# Microcontroller.net
KiCad netlist of a schematic drawn in Altium Designer
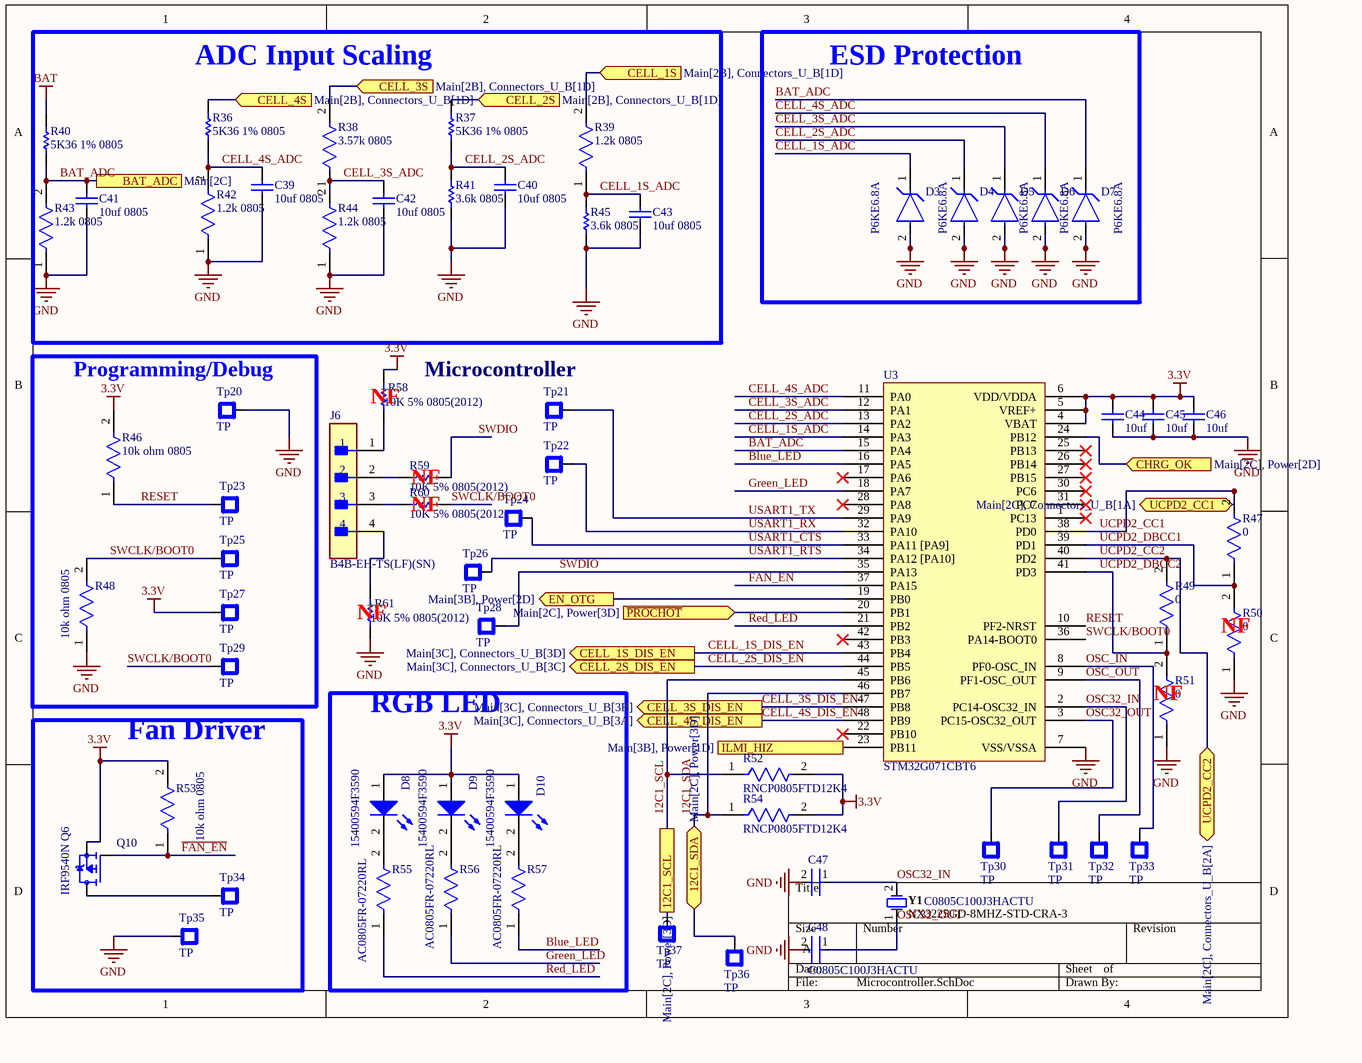
[diagram p0: Microcontroller.SchDoc]

(export (version "E")
  (design (tool "Eeschema 10.0.6"))
  (components
    (comp (ref "C39")
      (value "10uf 0805")
      (footprint "CAPC2013X145X50NL20T20")
      (fields (field (name "PART NUMBER") "VJ0805Y105KXQRW1BC") (field (name "MANUFACTURER") "Vitramon"))
      (libsource (lib "Altium Content Vault") (part "CAP"))
    )
    (comp (ref "C40")
      (value "10uf 0805")
      (footprint "CAPC2013X145X50NL20T20")
      (fields (field (name "PART NUMBER") "VJ0805Y105KXQRW1BC") (field (name "MANUFACTURER") "Vitramon"))
      (libsource (lib "Altium Content Vault") (part "CAP"))
    )
    (comp (ref "C41")
      (value "10uf 0805")
      (footprint "CAPC2013X145X50NL20T20")
      (fields (field (name "PART NUMBER") "VJ0805Y105KXQRW1BC") (field (name "MANUFACTURER") "Vitramon"))
      (libsource (lib "Altium Content Vault") (part "CAP"))
    )
    (comp (ref "C42")
      (value "10uf 0805")
      (footprint "CAPC2013X145X50NL20T20")
      (fields (field (name "PART NUMBER") "VJ0805Y105KXQRW1BC") (field (name "MANUFACTURER") "Vitramon"))
      (libsource (lib "Altium Content Vault") (part "CAP"))
    )
    (comp (ref "C43")
      (value "10uf 0805")
      (footprint "CAPC2013X145X50NL20T20")
      (fields (field (name "PART NUMBER") "VJ0805Y105KXQRW1BC") (field (name "MANUFACTURER") "Vitramon"))
      (libsource (lib "Altium Content Vault") (part "CAP"))
    )
    (comp (ref "C44")
      (value "10uf")
      (footprint "CAPC2013X145X50LL20T25")
      (fields (field (name "MANUFACTURER") "Kemet") (field (name "PART NUMBER") "C0805C106K8RACTU"))
      (libsource (lib "Altium Content Vault") (part "CAP"))
    )
    (comp (ref "C45")
      (value "10uf")
      (footprint "CAPC2013X145X50LL20T25")
      (fields (field (name "MANUFACTURER") "Kemet") (field (name "PART NUMBER") "C0805C106K8RACTU"))
      (libsource (lib "Altium Content Vault") (part "CAP"))
    )
    (comp (ref "C46")
      (value "10uf")
      (footprint "CAPC2013X145X50LL20T25")
      (fields (field (name "MANUFACTURER") "Kemet") (field (name "PART NUMBER") "C0805C106K8RACTU"))
      (libsource (lib "Altium Content Vault") (part "CAP"))
    )
    (comp (ref "C47")
      (value "C0805C100J3HACTU")
      (footprint "FP-C0805C-DN-MFG")
      (description "C0805 10 pF X8R 30ppm/°C 5.00% 25 V")
      (fields (field (name "TOLERANCE") "0.05") (field (name "MANUFACTURER") "KEMET"))
      (libsource (lib "Altium Content Vault") (part "b4654b650e69147ec39a6b967a45e02"))
    )
    (comp (ref "C48")
      (value "C0805C100J3HACTU")
      (footprint "FP-C0805C-DN-MFG")
      (description "C0805 10 pF X8R 30ppm/°C 5.00% 25 V")
      (fields (field (name "TOLERANCE") "0.05") (field (name "MANUFACTURER") "KEMET"))
      (libsource (lib "Altium Content Vault") (part "b4654b650e69147ec39a6b967a45e02"))
    )
    (comp (ref "D3")
      (value "P6KE6.8A")
      (footprint "FP-P6KE-MFG")
      (description "TVS DIODE 5.8V 10.5V DO204AC")
      (fields
        (field (name "MANUFACTURER") "Littelfuse Inc")
        (field (name "OCTOPART") "https://octopart.com/p6ke6.8a-littelfuse-20808")
      )
      (libsource (lib "Altium Content Vault") (part "f813f71cba58e380607f5dd3caf9714"))
    )
    (comp (ref "D4")
      (value "P6KE6.8A")
      (footprint "FP-P6KE-MFG")
      (description "TVS DIODE 5.8V 10.5V DO204AC")
      (fields
        (field (name "MANUFACTURER") "Littelfuse Inc")
        (field (name "OCTOPART") "https://octopart.com/p6ke6.8a-littelfuse-20808")
      )
      (libsource (lib "Altium Content Vault") (part "f813f71cba58e380607f5dd3caf9714"))
    )
    (comp (ref "D5")
      (value "P6KE6.8A")
      (footprint "FP-P6KE-MFG")
      (description "TVS DIODE 5.8V 10.5V DO204AC")
      (fields
        (field (name "MANUFACTURER") "Littelfuse Inc")
        (field (name "OCTOPART") "https://octopart.com/p6ke6.8a-littelfuse-20808")
      )
      (libsource (lib "Altium Content Vault") (part "f813f71cba58e380607f5dd3caf9714"))
    )
    (comp (ref "D6")
      (value "P6KE6.8A")
      (footprint "FP-P6KE-MFG")
      (description "TVS DIODE 5.8V 10.5V DO204AC")
      (fields
        (field (name "MANUFACTURER") "Littelfuse Inc")
        (field (name "OCTOPART") "https://octopart.com/p6ke6.8a-littelfuse-20808")
      )
      (libsource (lib "Altium Content Vault") (part "f813f71cba58e380607f5dd3caf9714"))
    )
    (comp (ref "D7")
      (value "P6KE6.8A")
      (footprint "FP-P6KE-MFG")
      (description "TVS DIODE 5.8V 10.5V DO204AC")
      (fields
        (field (name "MANUFACTURER") "Littelfuse Inc")
        (field (name "OCTOPART") "https://octopart.com/p6ke6.8a-littelfuse-20808")
      )
      (libsource (lib "Altium Content Vault") (part "f813f71cba58e380607f5dd3caf9714"))
    )
    (comp (ref "D8")
      (value "15400594F3590")
      (footprint "WL-TIRC_5mm")
      (description "Led, 5Mm, 940Nm, 30Mw/Sr, Th Rohs Compliant: Yes")
      (libsource (lib "Altium Content Vault") (part "LED_Infrared_1A-2K"))
    )
    (comp (ref "D9")
      (value "15400594F3590")
      (footprint "WL-TIRC_5mm")
      (description "Led, 5Mm, 940Nm, 30Mw/Sr, Th Rohs Compliant: Yes")
      (libsource (lib "Altium Content Vault") (part "LED_Infrared_1A-2K"))
    )
    (comp (ref "D10")
      (value "15400594F3590")
      (footprint "WL-TIRC_5mm")
      (description "Led, 5Mm, 940Nm, 30Mw/Sr, Th Rohs Compliant: Yes")
      (libsource (lib "Altium Content Vault") (part "LED_Infrared_1A-2K"))
    )
    (comp (ref "J6")
      (value "B4B-EH-TS(LF)(SN)")
      (footprint "FP-B4B-EH-TS_LF_SN-MFG")
      (description "CONN HEADER EH TOP 4POS 2.5MM")
      (libsource (lib "Altium Content Vault") (part "299a8cea1bdcbc3624fe62c390fa72c"))
    )
    (comp (ref "Q10")
      (value "IRF9540N Q6")
      (footprint "TO254P1041X444X1930-3")
      (description "P-Channel 100 V 23A (Tc) 3.1W (Ta), 110W (Tc)")
      (fields (field (name "MF") "Infineon Technologies") (field (name "MP") "IRF9540N"))
      (libsource (lib "power_schi") (part "IRF9540N Q6"))
    )
    (comp (ref "R36")
      (value "5K36 1% 0805")
      (footprint "RESC0805(2012)_M")
      (description "5K36 0.125W 1% 0805 (2012 Metric)  SMD")
      (fields (field (name "POWER") "0.125 W") (field (name "TOLERANCE") "1 %"))
      (libsource (lib "Altium Content Vault") (part "RES"))
    )
    (comp (ref "R37")
      (value "5K36 1% 0805")
      (footprint "RESC0805(2012)_M")
      (description "5K36 0.125W 1% 0805 (2012 Metric)  SMD")
      (fields (field (name "POWER") "0.125 W") (field (name "TOLERANCE") "1 %"))
      (libsource (lib "Altium Content Vault") (part "RES"))
    )
    (comp (ref "R38")
      (value "3.57k 0805")
      (footprint "FP-RT0805-MFG")
      (description "RES 357K OHM 1/8W .1% SMD 0805")
      (fields
        (field (name "OCTOPART") "https://octopart.com/rt0805brd07357kl-yageo-1483813")
        (field (name "MANUFACTURER") "Yageo")
      )
      (libsource (lib "Altium Content Vault") (part "1029c3af85768c4190bb7ad29bc67b5"))
    )
    (comp (ref "R39")
      (value "1.2k 0805")
      (footprint "FP-RMCF0805-IPC_A")
      (description "1.2kΩ ±5% 0.125W 0805 Thick Film Chip Resistor AEC-Q200 compliant")
      (fields (field (name "TOLERANCE") "5%"))
      (libsource (lib "Altium Content Vault") (part "1029c3af85768c4190bb7ad29bc67b5"))
    )
    (comp (ref "R40")
      (value "5K36 1% 0805")
      (footprint "RESC0805(2012)_M")
      (description "5K36 0.125W 1% 0805 (2012 Metric)  SMD")
      (fields (field (name "POWER") "0.125 W") (field (name "TOLERANCE") "1 %"))
      (libsource (lib "Altium Content Vault") (part "RES"))
    )
    (comp (ref "R41")
      (value "3.6k 0805")
      (footprint "RESC0805(2012)_L")
      (description "3K6 0.125W 5% 0805 (2012 Metric)  SMD")
      (fields (field (name "TOLERANCE") "5 %") (field (name "POWER") "0.125 W"))
      (libsource (lib "Altium Content Vault") (part "RES"))
    )
    (comp (ref "R42")
      (value "1.2k 0805")
      (footprint "FP-RMCF0805-IPC_A")
      (description "1.2kΩ ±5% 0.125W 0805 Thick Film Chip Resistor AEC-Q200 compliant")
      (fields (field (name "TOLERANCE") "5%"))
      (libsource (lib "Altium Content Vault") (part "1029c3af85768c4190bb7ad29bc67b5"))
    )
    (comp (ref "R43")
      (value "1.2k 0805")
      (footprint "FP-RMCF0805-IPC_A")
      (description "1.2kΩ ±5% 0.125W 0805 Thick Film Chip Resistor AEC-Q200 compliant")
      (fields (field (name "TOLERANCE") "5%"))
      (libsource (lib "Altium Content Vault") (part "1029c3af85768c4190bb7ad29bc67b5"))
    )
    (comp (ref "R44")
      (value "1.2k 0805")
      (footprint "FP-RMCF0805-IPC_A")
      (description "1.2kΩ ±5% 0.125W 0805 Thick Film Chip Resistor AEC-Q200 compliant")
      (fields (field (name "TOLERANCE") "5%"))
      (libsource (lib "Altium Content Vault") (part "1029c3af85768c4190bb7ad29bc67b5"))
    )
    (comp (ref "R45")
      (value "3.6k 0805")
      (footprint "RESC0805(2012)_L")
      (description "3K6 0.125W 5% 0805 (2012 Metric)  SMD")
      (fields (field (name "TOLERANCE") "5 %") (field (name "POWER") "0.125 W"))
      (libsource (lib "Altium Content Vault") (part "RES"))
    )
    (comp (ref "R46")
      (value "10k ohm 0805")
      (footprint "FP-MCU0805-IPC_C")
      (description "RES 1.05K OHM 0.5% 1/5W 0805")
      (fields (field (name "TOLERANCE") "0.1%"))
      (libsource (lib "Altium Content Vault") (part "1029c3af85768c4190bb7ad29bc67b5"))
    )
    (comp (ref "R47")
      (value "0")
      (footprint "FP-HCJ0805-MFG")
      (description "RES 0 OHM JUMPER 1/2W 0805")
      (libsource (lib "Altium Content Vault") (part "1029c3af85768c4190bb7ad29bc67b5"))
    )
    (comp (ref "R48")
      (value "10k ohm 0805")
      (footprint "FP-MCU0805-IPC_C")
      (description "RES 1.05K OHM 0.5% 1/5W 0805")
      (fields (field (name "TOLERANCE") "0.1%"))
      (libsource (lib "Altium Content Vault") (part "1029c3af85768c4190bb7ad29bc67b5"))
    )
    (comp (ref "R49")
      (value "0")
      (footprint "FP-HCJ0805-MFG")
      (description "RES 0 OHM JUMPER 1/2W 0805")
      (libsource (lib "Altium Content Vault") (part "1029c3af85768c4190bb7ad29bc67b5"))
    )
    (comp (ref "R50")
      (value "0")
      (footprint "FP-HCJ0805-MFG")
      (description "RES 0 OHM JUMPER 1/2W 0805")
      (libsource (lib "Altium Content Vault") (part "1029c3af85768c4190bb7ad29bc67b5"))
    )
    (comp (ref "R51")
      (value "0")
      (footprint "FP-HCJ0805-MFG")
      (description "RES 0 OHM JUMPER 1/2W 0805")
      (libsource (lib "Altium Content Vault") (part "1029c3af85768c4190bb7ad29bc67b5"))
    )
    (comp (ref "R52")
      (value "RNCP0805FTD12K4")
      (footprint "FP-RNCP0805-IPC_C")
      (description "12.4kΩ ±1% 0.25W 0805 High Power Anti-Sulfur Thin Film Chip Resistor")
      (fields (field (name "TOLERANCE") "1%"))
      (libsource (lib "Altium Content Vault") (part "1029c3af85768c4190bb7ad29bc67b5"))
    )
    (comp (ref "R53")
      (value "10k ohm 0805")
      (footprint "FP-MCU0805-IPC_C")
      (description "RES 1.05K OHM 0.5% 1/5W 0805")
      (fields (field (name "TOLERANCE") "0.1%"))
      (libsource (lib "Altium Content Vault") (part "1029c3af85768c4190bb7ad29bc67b5"))
    )
    (comp (ref "R54")
      (value "RNCP0805FTD12K4")
      (footprint "FP-RNCP0805-IPC_C")
      (description "12.4kΩ ±1% 0.25W 0805 High Power Anti-Sulfur Thin Film Chip Resistor")
      (fields (field (name "TOLERANCE") "1%"))
      (libsource (lib "Altium Content Vault") (part "1029c3af85768c4190bb7ad29bc67b5"))
    )
    (comp (ref "R55")
      (value "AC0805FR-07220RL")
      (footprint "FP-AC0805-MFG")
      (description "RES SMD 220 OHM 1% 1/8W 0805")
      (fields
        (field (name "OCTOPART") "https://octopart.com/ac0805fr-07220rl-yageo-26041145")
        (field (name "TOLERANCE") "0.01")
      )
      (libsource (lib "Altium Content Vault") (part "1029c3af85768c4190bb7ad29bc67b5"))
    )
    (comp (ref "R56")
      (value "AC0805FR-07220RL")
      (footprint "FP-AC0805-MFG")
      (description "RES SMD 220 OHM 1% 1/8W 0805")
      (fields
        (field (name "OCTOPART") "https://octopart.com/ac0805fr-07220rl-yageo-26041145")
        (field (name "TOLERANCE") "0.01")
      )
      (libsource (lib "Altium Content Vault") (part "1029c3af85768c4190bb7ad29bc67b5"))
    )
    (comp (ref "R57")
      (value "AC0805FR-07220RL")
      (footprint "FP-AC0805-MFG")
      (description "RES SMD 220 OHM 1% 1/8W 0805")
      (fields
        (field (name "OCTOPART") "https://octopart.com/ac0805fr-07220rl-yageo-26041145")
        (field (name "TOLERANCE") "0.01")
      )
      (libsource (lib "Altium Content Vault") (part "1029c3af85768c4190bb7ad29bc67b5"))
    )
    (comp (ref "R58")
      (value "10K 5% 0805(2012)")
      (footprint "RESC0805(2012)_L")
      (description "10K 0.125W 5% 0805 (2012 Metric)  SMD")
      (fields (field (name "POWER") "0.125 W") (field (name "TOLERANCE") "5 %"))
      (libsource (lib "Altium Content Vault") (part "RES"))
    )
    (comp (ref "R59")
      (value "10K 5% 0805(2012)")
      (footprint "RESC0805(2012)_L")
      (description "10K 0.125W 5% 0805 (2012 Metric)  SMD")
      (fields (field (name "POWER") "0.125 W") (field (name "TOLERANCE") "5 %"))
      (libsource (lib "Altium Content Vault") (part "RES"))
    )
    (comp (ref "R60")
      (value "10K 5% 0805(2012)")
      (footprint "RESC0805(2012)_L")
      (description "10K 0.125W 5% 0805 (2012 Metric)  SMD")
      (fields (field (name "POWER") "0.125 W") (field (name "TOLERANCE") "5 %"))
      (libsource (lib "Altium Content Vault") (part "RES"))
    )
    (comp (ref "R61")
      (value "10K 5% 0805(2012)")
      (footprint "RESC0805(2012)_L")
      (description "10K 0.125W 5% 0805 (2012 Metric)  SMD")
      (fields (field (name "POWER") "0.125 W") (field (name "TOLERANCE") "5 %"))
      (libsource (lib "Altium Content Vault") (part "RES"))
    )
    (comp (ref "Tp20") (value "TP") (footprint "Tp") (libsource (lib "power_schi") (part "TP")))
    (comp (ref "Tp21") (value "TP") (footprint "Tp") (libsource (lib "power_schi") (part "TP")))
    (comp (ref "Tp22") (value "TP") (footprint "Tp") (libsource (lib "power_schi") (part "TP")))
    (comp (ref "Tp23") (value "TP") (footprint "Tp") (libsource (lib "power_schi") (part "TP")))
    (comp (ref "Tp24") (value "TP") (footprint "Tp") (libsource (lib "power_schi") (part "TP")))
    (comp (ref "Tp25") (value "TP") (footprint "Tp") (libsource (lib "power_schi") (part "TP")))
    (comp (ref "Tp26") (value "TP") (footprint "Tp") (libsource (lib "power_schi") (part "TP")))
    (comp (ref "Tp27") (value "TP") (footprint "Tp") (libsource (lib "power_schi") (part "TP")))
    (comp (ref "Tp28") (value "TP") (footprint "Tp") (libsource (lib "power_schi") (part "TP")))
    (comp (ref "Tp29") (value "TP") (footprint "Tp") (libsource (lib "power_schi") (part "TP")))
    (comp (ref "Tp30") (value "TP") (footprint "Tp") (libsource (lib "power_schi") (part "TP")))
    (comp (ref "Tp31") (value "TP") (footprint "Tp") (libsource (lib "power_schi") (part "TP")))
    (comp (ref "Tp32") (value "TP") (footprint "Tp") (libsource (lib "power_schi") (part "TP")))
    (comp (ref "Tp33") (value "TP") (footprint "Tp") (libsource (lib "power_schi") (part "TP")))
    (comp (ref "Tp34") (value "TP") (footprint "Tp") (libsource (lib "power_schi") (part "TP")))
    (comp (ref "Tp35") (value "TP") (footprint "Tp") (libsource (lib "power_schi") (part "TP")))
    (comp (ref "Tp36") (value "TP") (footprint "Tp") (libsource (lib "power_schi") (part "TP")))
    (comp (ref "Tp37") (value "TP") (footprint "Tp") (libsource (lib "power_schi") (part "TP")))
    (comp (ref "U3")
      (value "STM32G071CBT6")
      (footprint "QFP50P900X900X160-48N")
      (description "MCU 32-bit ARM Cortex M0+ RISC 128KB Flash 1.8V/2.5V/3.3V 48-Pin LQFP Tray")
      (fields (field (name "MANUFACTURER") "STMicroelectronics"))
      (libsource (lib "power_schi") (part "STM32G071CBT6"))
    )
    (comp (ref "Y1")
      (value "NX3225GD-8MHZ-STD-CRA-3")
      (footprint "NDK-NX3225GD-8MHZ-STD-CRA-3_V")
      (description "Crystal Unit, 8 MHz, 8 pF, -40 to 150 degC, 2-Pin SMD, RoHS, Tape and Reel")
      (fields (field (name "MANUFACTURER") "NDK"))
      (libsource (lib "Altium Content Vault") (part "XTAL-1-2-2"))
    )
  )
  (nets
    (net (code "1") (name "/12C1_SCL") (class "Default")
      (node (ref "R52") (pin "1") (pinfunction "1_1") (pintype "passive"))
      (node (ref "Tp37") (pin "1") (pinfunction "1_1") (pintype "passive"))
      (node (ref "U3") (pin "45") (pinfunction "PB6_45") (pintype "passive"))
    )
    (net (code "2") (name "/12C1_SDA") (class "Default")
      (node (ref "R54") (pin "1") (pinfunction "1_1") (pintype "passive"))
      (node (ref "Tp36") (pin "1") (pinfunction "1_1") (pintype "passive"))
      (node (ref "U3") (pin "46") (pinfunction "PB7_46") (pintype "passive"))
    )
    (net (code "3") (name "/BAT_ADC") (class "Default")
      (node (ref "C41") (pin "2") (pinfunction "2_2") (pintype "passive"))
      (node (ref "D7") (pin "1") (pinfunction "C_1") (pintype "passive"))
      (node (ref "R40") (pin "1") (pinfunction "1_1") (pintype "passive"))
      (node (ref "R43") (pin "2") (pinfunction "2_2") (pintype "passive"))
      (node (ref "U3") (pin "15") (pinfunction "PA4_15") (pintype "passive"))
    )
    (net (code "4") (name "/Blue_LED") (class "Default")
      (node (ref "R57") (pin "1") (pinfunction "1_1") (pintype "passive"))
      (node (ref "U3") (pin "16") (pinfunction "PA5_16") (pintype "passive"))
    )
    (net (code "5") (name "/CELL_1S") (class "Default")
      (node (ref "R39") (pin "2") (pinfunction "2_2") (pintype "passive"))
    )
    (net (code "6") (name "/CELL_1S_ADC") (class "Default")
      (node (ref "C43") (pin "2") (pinfunction "2_2") (pintype "passive"))
      (node (ref "D3") (pin "1") (pinfunction "C_1") (pintype "passive"))
      (node (ref "R39") (pin "1") (pinfunction "1_1") (pintype "passive"))
      (node (ref "R45") (pin "2") (pinfunction "2_2") (pintype "passive"))
      (node (ref "U3") (pin "14") (pinfunction "PA3_14") (pintype "passive"))
    )
    (net (code "7") (name "/CELL_1S_DIS_EN") (class "Default")
      (node (ref "U3") (pin "43") (pinfunction "PB4_43") (pintype "passive"))
    )
    (net (code "8") (name "/CELL_2S") (class "Default")
      (node (ref "R37") (pin "2") (pinfunction "2_2") (pintype "passive"))
    )
    (net (code "9") (name "/CELL_2S_ADC") (class "Default")
      (node (ref "C40") (pin "2") (pinfunction "2_2") (pintype "passive"))
      (node (ref "D4") (pin "1") (pinfunction "C_1") (pintype "passive"))
      (node (ref "R37") (pin "1") (pinfunction "1_1") (pintype "passive"))
      (node (ref "R41") (pin "2") (pinfunction "2_2") (pintype "passive"))
      (node (ref "U3") (pin "13") (pinfunction "PA2_13") (pintype "passive"))
    )
    (net (code "10") (name "/CELL_2S_DIS_EN") (class "Default")
      (node (ref "U3") (pin "44") (pinfunction "PB5_44") (pintype "passive"))
    )
    (net (code "11") (name "/CELL_3S") (class "Default")
      (node (ref "R38") (pin "2") (pinfunction "2_2") (pintype "passive"))
    )
    (net (code "12") (name "/CELL_3S_ADC") (class "Default")
      (node (ref "C42") (pin "2") (pinfunction "2_2") (pintype "passive"))
      (node (ref "D5") (pin "1") (pinfunction "C_1") (pintype "passive"))
      (node (ref "R38") (pin "1") (pinfunction "1_1") (pintype "passive"))
      (node (ref "R44") (pin "2") (pinfunction "2_2") (pintype "passive"))
      (node (ref "U3") (pin "12") (pinfunction "PA1_12") (pintype "passive"))
    )
    (net (code "13") (name "/CELL_3S_DIS_EN") (class "Default")
      (node (ref "U3") (pin "47") (pinfunction "PB8_47") (pintype "passive"))
    )
    (net (code "14") (name "/CELL_4S") (class "Default")
      (node (ref "R36") (pin "2") (pinfunction "2_2") (pintype "passive"))
    )
    (net (code "15") (name "/CELL_4S_ADC") (class "Default")
      (node (ref "C39") (pin "2") (pinfunction "2_2") (pintype "passive"))
      (node (ref "D6") (pin "1") (pinfunction "C_1") (pintype "passive"))
      (node (ref "R36") (pin "1") (pinfunction "1_1") (pintype "passive"))
      (node (ref "R42") (pin "2") (pinfunction "2_2") (pintype "passive"))
      (node (ref "U3") (pin "11") (pinfunction "PA0_11") (pintype "passive"))
    )
    (net (code "16") (name "/CELL_4S_DIS_EN") (class "Default")
      (node (ref "U3") (pin "48") (pinfunction "PB9_48") (pintype "passive"))
    )
    (net (code "17") (name "/CHRG_OK") (class "Default")
      (node (ref "U3") (pin "24") (pinfunction "PB12_24") (pintype "passive"))
    )
    (net (code "18") (name "/EN_OTG") (class "Default")
      (node (ref "U3") (pin "19") (pinfunction "PB0_19") (pintype "passive"))
    )
    (net (code "19") (name "/Green_LED") (class "Default")
      (node (ref "R56") (pin "1") (pinfunction "1_1") (pintype "passive"))
      (node (ref "U3") (pin "18") (pinfunction "PA7_18") (pintype "passive"))
    )
    (net (code "20") (name "/ILMI_HIZ") (class "Default")
      (node (ref "U3") (pin "23") (pinfunction "PB11_23") (pintype "passive"))
    )
    (net (code "21") (name "/OSC32_IN") (class "Default")
      (node (ref "C47") (pin "1") (pinfunction "1_1") (pintype "passive"))
      (node (ref "Tp31") (pin "1") (pinfunction "1_1") (pintype "passive"))
      (node (ref "U3") (pin "2") (pinfunction "PC14-OSC32_IN_2") (pintype "passive"))
      (node (ref "Y1") (pin "2") (pinfunction "2_2") (pintype "passive"))
    )
    (net (code "22") (name "/OSC32_OUT") (class "Default")
      (node (ref "C48") (pin "1") (pinfunction "1_1") (pintype "passive"))
      (node (ref "Tp30") (pin "1") (pinfunction "1_1") (pintype "passive"))
      (node (ref "U3") (pin "3") (pinfunction "PC15-OSC32_OUT_3") (pintype "passive"))
      (node (ref "Y1") (pin "1") (pinfunction "1_1") (pintype "passive"))
    )
    (net (code "23") (name "/OSC_IN") (class "Default")
      (node (ref "Tp33") (pin "1") (pinfunction "1_1") (pintype "passive"))
      (node (ref "U3") (pin "8") (pinfunction "PF0-OSC_IN_8") (pintype "passive"))
    )
    (net (code "24") (name "/OSC_OUT") (class "Default")
      (node (ref "Tp32") (pin "1") (pinfunction "1_1") (pintype "passive"))
      (node (ref "U3") (pin "9") (pinfunction "PF1-OSC_OUT_9") (pintype "passive"))
    )
    (net (code "25") (name "/RESET") (class "Default")
      (node (ref "R46") (pin "1") (pinfunction "1_1") (pintype "passive"))
      (node (ref "Tp23") (pin "1") (pinfunction "1_1") (pintype "passive"))
      (node (ref "U3") (pin "10") (pinfunction "PF2-NRST_10") (pintype "passive"))
    )
    (net (code "26") (name "/Red_LED") (class "Default")
      (node (ref "R55") (pin "1") (pinfunction "1_1") (pintype "passive"))
      (node (ref "U3") (pin "21") (pinfunction "PB2_21") (pintype "passive"))
    )
    (net (code "27") (name "/SWCLK{slash}BOOT0") (class "Default")
      (node (ref "R48") (pin "2") (pinfunction "2_2") (pintype "passive"))
      (node (ref "R60") (pin "2") (pinfunction "2_2") (pintype "passive"))
      (node (ref "Tp25") (pin "1") (pinfunction "1_1") (pintype "passive"))
      (node (ref "Tp29") (pin "1") (pinfunction "1_1") (pintype "passive"))
      (node (ref "U3") (pin "36") (pinfunction "PA14-BOOT0_36") (pintype "passive"))
    )
    (net (code "28") (name "/SWDIO") (class "Default")
      (node (ref "R59") (pin "2") (pinfunction "2_2") (pintype "passive"))
      (node (ref "Tp28") (pin "1") (pinfunction "1_1") (pintype "passive"))
      (node (ref "U3") (pin "35") (pinfunction "PA13_35") (pintype "passive"))
    )
    (net (code "29") (name "/UCPD2_CC1") (class "Default")
      (node (ref "R47") (pin "2") (pinfunction "2_2") (pintype "passive"))
      (node (ref "U3") (pin "38") (pinfunction "PD0_38") (pintype "passive"))
    )
    (net (code "30") (name "/UCPD2_CC2") (class "Default")
      (node (ref "R49") (pin "2") (pinfunction "2_2") (pintype "passive"))
      (node (ref "U3") (pin "40") (pinfunction "PD2_40") (pintype "passive"))
    )
    (net (code "31") (name "/UCPD2_DBCC1") (class "Default")
      (node (ref "R47") (pin "1") (pinfunction "1_1") (pintype "passive"))
      (node (ref "R50") (pin "2") (pinfunction "2_2") (pintype "passive"))
      (node (ref "U3") (pin "39") (pinfunction "PD1_39") (pintype "passive"))
    )
    (net (code "32") (name "/UCPD2_DBCC2") (class "Default")
      (node (ref "R49") (pin "1") (pinfunction "1_1") (pintype "passive"))
      (node (ref "R51") (pin "2") (pinfunction "2_2") (pintype "passive"))
      (node (ref "U3") (pin "41") (pinfunction "PD3_41") (pintype "passive"))
    )
    (net (code "33") (name "/USART1_CTS") (class "Default")
      (node (ref "Tp24") (pin "1") (pinfunction "1_1") (pintype "passive"))
      (node (ref "U3") (pin "33") (pinfunction "PA11_[PA9]_33") (pintype "passive"))
    )
    (net (code "34") (name "/USART1_RTS") (class "Default")
      (node (ref "Tp26") (pin "1") (pinfunction "1_1") (pintype "passive"))
      (node (ref "U3") (pin "34") (pinfunction "PA12_[PA10]_34") (pintype "passive"))
    )
    (net (code "35") (name "/USART1_RX") (class "Default")
      (node (ref "Tp22") (pin "1") (pinfunction "1_1") (pintype "passive"))
      (node (ref "U3") (pin "32") (pinfunction "PA10_32") (pintype "passive"))
    )
    (net (code "36") (name "/USART1_TX") (class "Default")
      (node (ref "Tp21") (pin "1") (pinfunction "1_1") (pintype "passive"))
      (node (ref "U3") (pin "29") (pinfunction "PA9_29") (pintype "passive"))
    )
    (net (code "37") (name "/~{FAN_EN}") (class "Default")
      (node (ref "Q10") (pin "1") (pinfunction "G_1") (pintype "passive"))
      (node (ref "R53") (pin "1") (pinfunction "1_1") (pintype "passive"))
      (node (ref "U3") (pin "37") (pinfunction "PA15_37") (pintype "passive"))
    )
    (net (code "38") (name "/~{PROCHOT}") (class "Default")
      (node (ref "U3") (pin "20") (pinfunction "PB1_20") (pintype "passive"))
    )
    (net (code "39") (name "3.3V") (class "Default")
      (node (ref "C44") (pin "2") (pinfunction "2_2") (pintype "passive"))
      (node (ref "C45") (pin "2") (pinfunction "2_2") (pintype "passive"))
      (node (ref "C46") (pin "2") (pinfunction "2_2") (pintype "passive"))
      (node (ref "D10") (pin "1") (pinfunction "A_1") (pintype "passive"))
      (node (ref "D8") (pin "1") (pinfunction "A_1") (pintype "passive"))
      (node (ref "D9") (pin "1") (pinfunction "A_1") (pintype "passive"))
      (node (ref "Q10") (pin "3") (pinfunction "S_3") (pintype "passive"))
      (node (ref "R46") (pin "2") (pinfunction "2_2") (pintype "passive"))
      (node (ref "R52") (pin "2") (pinfunction "2_2") (pintype "passive"))
      (node (ref "R53") (pin "2") (pinfunction "2_2") (pintype "passive"))
      (node (ref "R54") (pin "2") (pinfunction "2_2") (pintype "passive"))
      (node (ref "R58") (pin "2") (pinfunction "2_2") (pintype "passive"))
      (node (ref "Tp27") (pin "1") (pinfunction "1_1") (pintype "passive"))
      (node (ref "U3") (pin "4") (pinfunction "VBAT_4") (pintype "passive"))
      (node (ref "U3") (pin "5") (pinfunction "VREF+_5") (pintype "passive"))
      (node (ref "U3") (pin "6") (pinfunction "VDD/VDDA_6") (pintype "passive"))
    )
    (net (code "40") (name "BAT") (class "Default")
      (node (ref "R40") (pin "2") (pinfunction "2_2") (pintype "passive"))
    )
    (net (code "41") (name "GND") (class "Default")
      (node (ref "C39") (pin "1") (pinfunction "1_1") (pintype "passive"))
      (node (ref "C40") (pin "1") (pinfunction "1_1") (pintype "passive"))
      (node (ref "C41") (pin "1") (pinfunction "1_1") (pintype "passive"))
      (node (ref "C42") (pin "1") (pinfunction "1_1") (pintype "passive"))
      (node (ref "C43") (pin "1") (pinfunction "1_1") (pintype "passive"))
      (node (ref "C44") (pin "1") (pinfunction "1_1") (pintype "passive"))
      (node (ref "C45") (pin "1") (pinfunction "1_1") (pintype "passive"))
      (node (ref "C46") (pin "1") (pinfunction "1_1") (pintype "passive"))
      (node (ref "C47") (pin "2") (pinfunction "2_2") (pintype "passive"))
      (node (ref "C48") (pin "2") (pinfunction "2_2") (pintype "passive"))
      (node (ref "D3") (pin "2") (pinfunction "A_2") (pintype "passive"))
      (node (ref "D4") (pin "2") (pinfunction "A_2") (pintype "passive"))
      (node (ref "D5") (pin "2") (pinfunction "A_2") (pintype "passive"))
      (node (ref "D6") (pin "2") (pinfunction "A_2") (pintype "passive"))
      (node (ref "D7") (pin "2") (pinfunction "A_2") (pintype "passive"))
      (node (ref "R41") (pin "1") (pinfunction "1_1") (pintype "passive"))
      (node (ref "R42") (pin "1") (pinfunction "1_1") (pintype "passive"))
      (node (ref "R43") (pin "1") (pinfunction "1_1") (pintype "passive"))
      (node (ref "R44") (pin "1") (pinfunction "1_1") (pintype "passive"))
      (node (ref "R45") (pin "1") (pinfunction "1_1") (pintype "passive"))
      (node (ref "R48") (pin "1") (pinfunction "1_1") (pintype "passive"))
      (node (ref "R50") (pin "1") (pinfunction "1_1") (pintype "passive"))
      (node (ref "R51") (pin "1") (pinfunction "1_1") (pintype "passive"))
      (node (ref "R61") (pin "1") (pinfunction "1_1") (pintype "passive"))
      (node (ref "Tp20") (pin "1") (pinfunction "1_1") (pintype "passive"))
      (node (ref "Tp35") (pin "1") (pinfunction "1_1") (pintype "passive"))
      (node (ref "U3") (pin "7") (pinfunction "VSS/VSSA_7") (pintype "passive"))
    )
    (net (code "42") (name "Net-(D8-K)") (class "Default")
      (node (ref "D8") (pin "2") (pinfunction "K_2") (pintype "passive"))
      (node (ref "R55") (pin "2") (pinfunction "2_2") (pintype "passive"))
    )
    (net (code "43") (name "Net-(D9-K)") (class "Default")
      (node (ref "D9") (pin "2") (pinfunction "K_2") (pintype "passive"))
      (node (ref "R56") (pin "2") (pinfunction "2_2") (pintype "passive"))
    )
    (net (code "44") (name "Net-(D10-K)") (class "Default")
      (node (ref "D10") (pin "2") (pinfunction "K_2") (pintype "passive"))
      (node (ref "R57") (pin "2") (pinfunction "2_2") (pintype "passive"))
    )
    (net (code "45") (name "Net-(J6-Pad1)") (class "Default")
      (node (ref "J6") (pin "1") (pinfunction "1_1") (pintype "passive"))
      (node (ref "R58") (pin "1") (pinfunction "1_1") (pintype "passive"))
    )
    (net (code "46") (name "Net-(J6-Pad2)") (class "Default")
      (node (ref "J6") (pin "2") (pinfunction "2_2") (pintype "passive"))
      (node (ref "R59") (pin "1") (pinfunction "1_1") (pintype "passive"))
    )
    (net (code "47") (name "Net-(J6-Pad3)") (class "Default")
      (node (ref "J6") (pin "3") (pinfunction "3_3") (pintype "passive"))
      (node (ref "R60") (pin "1") (pinfunction "1_1") (pintype "passive"))
    )
    (net (code "48") (name "Net-(J6-Pad4)") (class "Default")
      (node (ref "J6") (pin "4") (pinfunction "4_4") (pintype "passive"))
      (node (ref "R61") (pin "2") (pinfunction "2_2") (pintype "passive"))
    )
    (net (code "49") (name "Net-(Q10-D)") (class "Default")
      (node (ref "Q10") (pin "2") (pinfunction "D_2") (pintype "passive"))
      (node (ref "Tp34") (pin "1") (pinfunction "1_1") (pintype "passive"))
    )
    (net (code "50") (name "unconnected-(U3-PA6-Pad17)") (class "Default")
      (node (ref "U3") (pin "17") (pinfunction "PA6_17") (pintype "passive+no_connect"))
    )
    (net (code "51") (name "unconnected-(U3-PA8-Pad28)") (class "Default")
      (node (ref "U3") (pin "28") (pinfunction "PA8_28") (pintype "passive+no_connect"))
    )
    (net (code "52") (name "unconnected-(U3-PB3-Pad42)") (class "Default")
      (node (ref "U3") (pin "42") (pinfunction "PB3_42") (pintype "passive+no_connect"))
    )
    (net (code "53") (name "unconnected-(U3-PB10-Pad22)") (class "Default")
      (node (ref "U3") (pin "22") (pinfunction "PB10_22") (pintype "passive+no_connect"))
    )
    (net (code "54") (name "unconnected-(U3-PB13-Pad25)") (class "Default")
      (node (ref "U3") (pin "25") (pinfunction "PB13_25") (pintype "passive+no_connect"))
    )
    (net (code "55") (name "unconnected-(U3-PB14-Pad26)") (class "Default")
      (node (ref "U3") (pin "26") (pinfunction "PB14_26") (pintype "passive+no_connect"))
    )
    (net (code "56") (name "unconnected-(U3-PB15-Pad27)") (class "Default")
      (node (ref "U3") (pin "27") (pinfunction "PB15_27") (pintype "passive+no_connect"))
    )
    (net (code "57") (name "unconnected-(U3-PC6-Pad30)") (class "Default")
      (node (ref "U3") (pin "30") (pinfunction "PC6_30") (pintype "passive+no_connect"))
    )
    (net (code "58") (name "unconnected-(U3-PC7-Pad31)") (class "Default")
      (node (ref "U3") (pin "31") (pinfunction "PC7_31") (pintype "passive+no_connect"))
    )
    (net (code "59") (name "unconnected-(U3-PC13-Pad1)") (class "Default")
      (node (ref "U3") (pin "1") (pinfunction "PC13_1") (pintype "passive+no_connect"))
    )
  )
)
